# M507X.net
KiCad netlist of a schematic drawn in EAGLE
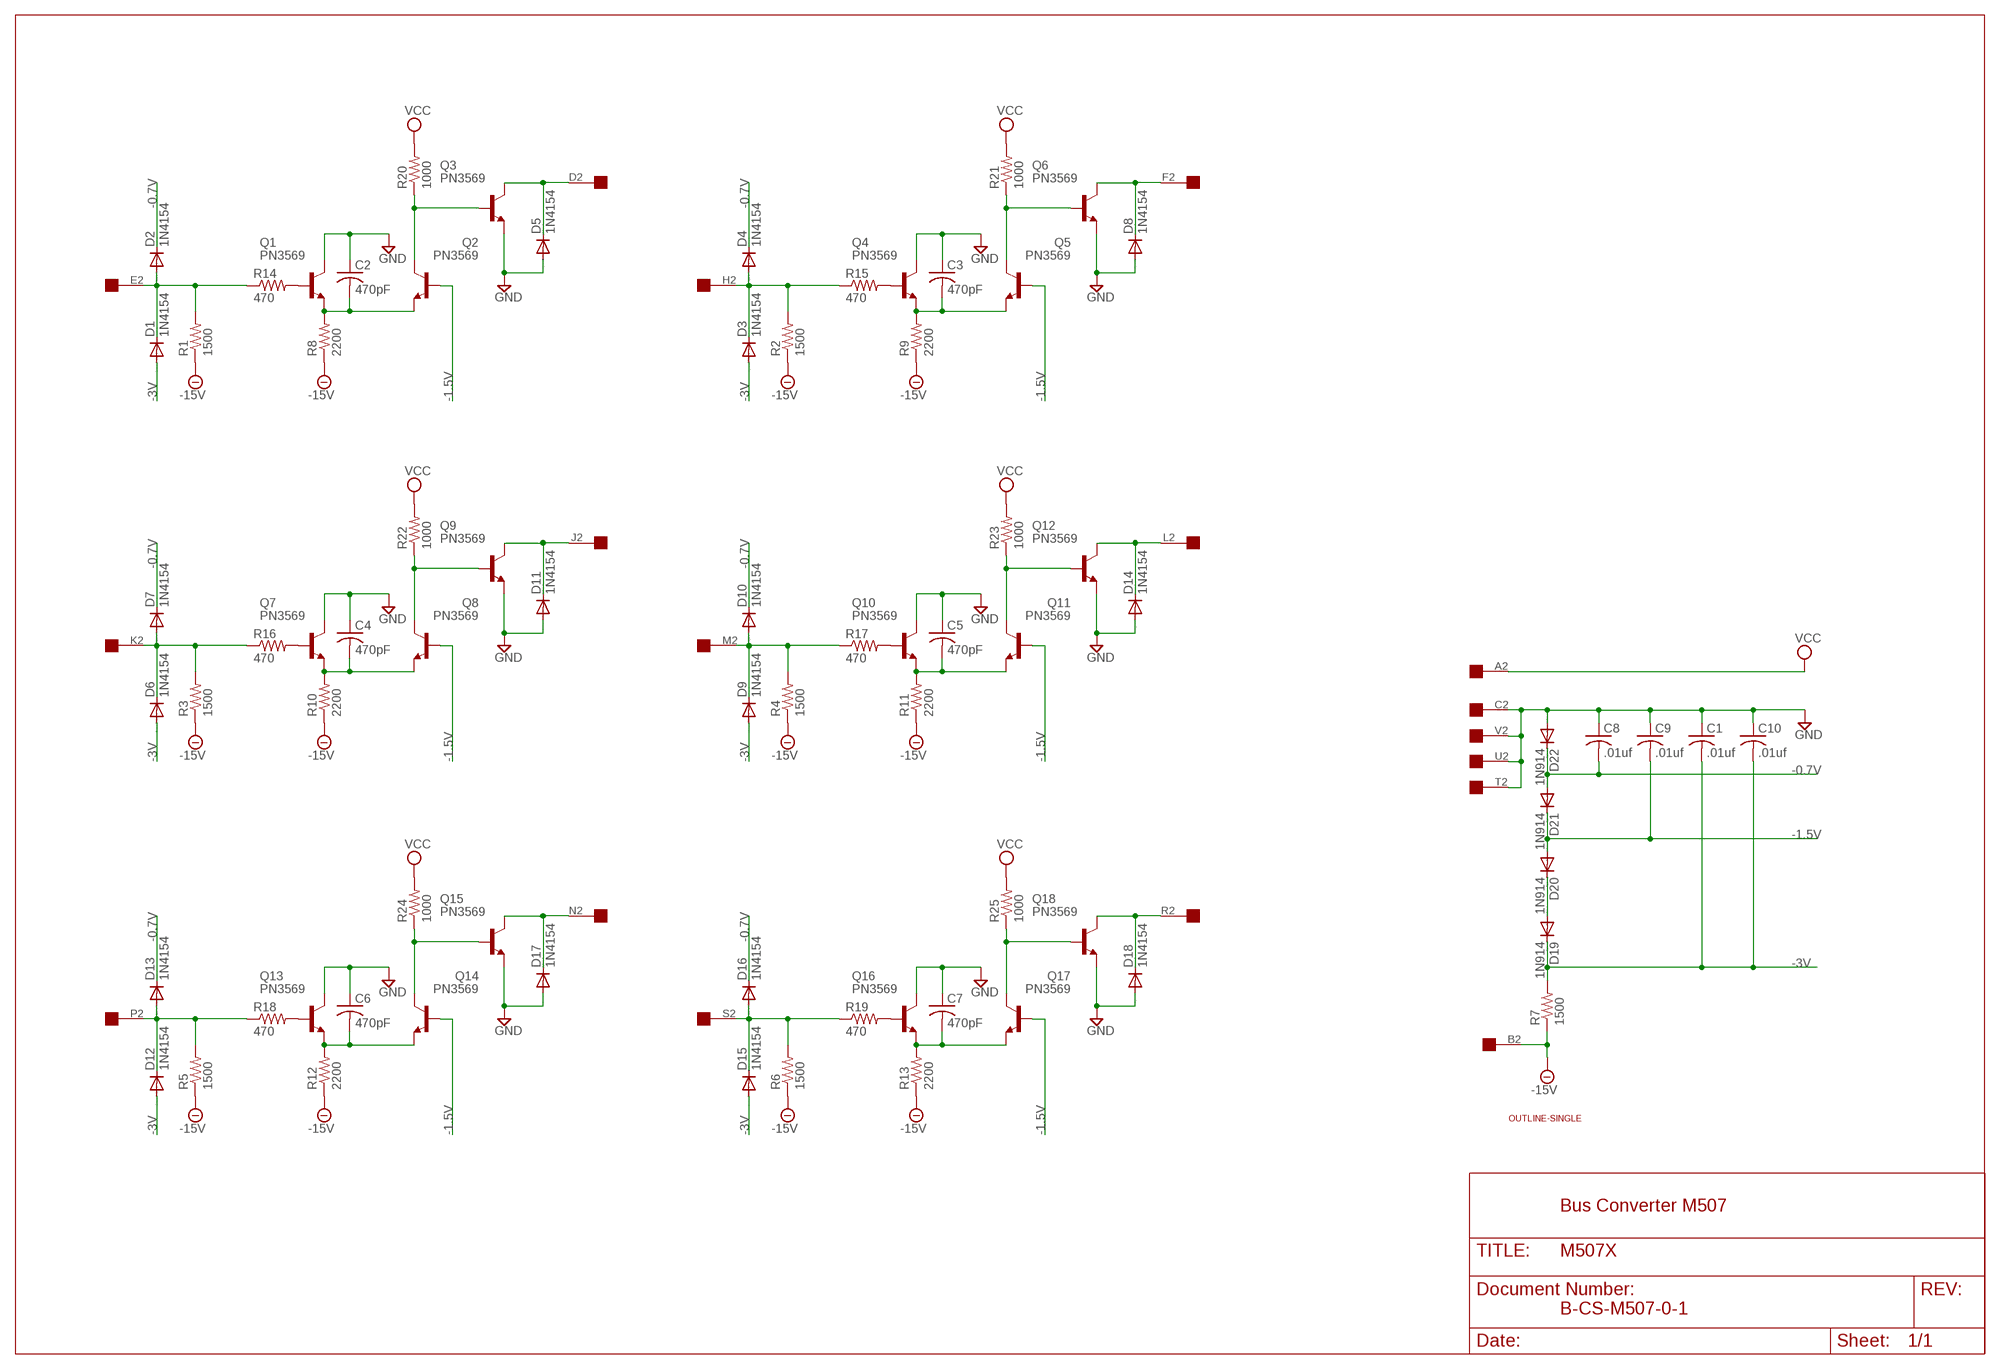
[diagram p0: schematic, sheet 1]

(export (version "E")
  (design (tool "Eeschema 10.0.6"))
  (components
    (comp (ref "C1")
      (value ".01uf")
      (footprint "eagle-import:C050-025X075")
      (libsource (lib "eagle-import") (part "C-US050-025X075"))
    )
    (comp (ref "C2")
      (value "470pF")
      (footprint "eagle-import:C050-025X075")
      (libsource (lib "eagle-import") (part "C-US050-025X075"))
    )
    (comp (ref "C3")
      (value "470pF")
      (footprint "eagle-import:C050-025X075")
      (libsource (lib "eagle-import") (part "C-US050-025X075"))
    )
    (comp (ref "C4")
      (value "470pF")
      (footprint "eagle-import:C050-025X075")
      (libsource (lib "eagle-import") (part "C-US050-025X075"))
    )
    (comp (ref "C5")
      (value "470pF")
      (footprint "eagle-import:C050-025X075")
      (libsource (lib "eagle-import") (part "C-US050-025X075"))
    )
    (comp (ref "C6")
      (value "470pF")
      (footprint "eagle-import:C050-025X075")
      (libsource (lib "eagle-import") (part "C-US050-025X075"))
    )
    (comp (ref "C7")
      (value "470pF")
      (footprint "eagle-import:C050-025X075")
      (libsource (lib "eagle-import") (part "C-US050-025X075"))
    )
    (comp (ref "C8")
      (value ".01uf")
      (footprint "eagle-import:C050-025X075")
      (libsource (lib "eagle-import") (part "C-US050-025X075"))
    )
    (comp (ref "C9")
      (value ".01uf")
      (footprint "eagle-import:C050-025X075")
      (libsource (lib "eagle-import") (part "C-US050-025X075"))
    )
    (comp (ref "C10")
      (value ".01uf")
      (footprint "eagle-import:C050-025X075")
      (libsource (lib "eagle-import") (part "C-US050-025X075"))
    )
    (comp (ref "D1")
      (value "1N4154")
      (footprint "eagle-import:DO35-10")
      (libsource (lib "eagle-import") (part "1N4148DO35-10"))
    )
    (comp (ref "D2")
      (value "1N4154")
      (footprint "eagle-import:DO35-10")
      (libsource (lib "eagle-import") (part "1N4148DO35-10"))
    )
    (comp (ref "D3")
      (value "1N4154")
      (footprint "eagle-import:DO35-10")
      (libsource (lib "eagle-import") (part "1N4148DO35-10"))
    )
    (comp (ref "D4")
      (value "1N4154")
      (footprint "eagle-import:DO35-10")
      (libsource (lib "eagle-import") (part "1N4148DO35-10"))
    )
    (comp (ref "D5")
      (value "1N4154")
      (footprint "eagle-import:DO35-10")
      (libsource (lib "eagle-import") (part "1N4148DO35-10"))
    )
    (comp (ref "D6")
      (value "1N4154")
      (footprint "eagle-import:DO35-10")
      (libsource (lib "eagle-import") (part "1N4148DO35-10"))
    )
    (comp (ref "D7")
      (value "1N4154")
      (footprint "eagle-import:DO35-10")
      (libsource (lib "eagle-import") (part "1N4148DO35-10"))
    )
    (comp (ref "D8")
      (value "1N4154")
      (footprint "eagle-import:DO35-10")
      (libsource (lib "eagle-import") (part "1N4148DO35-10"))
    )
    (comp (ref "D9")
      (value "1N4154")
      (footprint "eagle-import:DO35-10")
      (libsource (lib "eagle-import") (part "1N4148DO35-10"))
    )
    (comp (ref "D10")
      (value "1N4154")
      (footprint "eagle-import:DO35-10")
      (libsource (lib "eagle-import") (part "1N4148DO35-10"))
    )
    (comp (ref "D11")
      (value "1N4154")
      (footprint "eagle-import:DO35-10")
      (libsource (lib "eagle-import") (part "1N4148DO35-10"))
    )
    (comp (ref "D12")
      (value "1N4154")
      (footprint "eagle-import:DO35-10")
      (libsource (lib "eagle-import") (part "1N4148DO35-10"))
    )
    (comp (ref "D13")
      (value "1N4154")
      (footprint "eagle-import:DO35-10")
      (libsource (lib "eagle-import") (part "1N4148DO35-10"))
    )
    (comp (ref "D14")
      (value "1N4154")
      (footprint "eagle-import:DO35-10")
      (libsource (lib "eagle-import") (part "1N4148DO35-10"))
    )
    (comp (ref "D15")
      (value "1N4154")
      (footprint "eagle-import:DO35-10")
      (libsource (lib "eagle-import") (part "1N4148DO35-10"))
    )
    (comp (ref "D16")
      (value "1N4154")
      (footprint "eagle-import:DO35-10")
      (libsource (lib "eagle-import") (part "1N4148DO35-10"))
    )
    (comp (ref "D17")
      (value "1N4154")
      (footprint "eagle-import:DO35-10")
      (libsource (lib "eagle-import") (part "1N4148DO35-10"))
    )
    (comp (ref "D18")
      (value "1N4154")
      (footprint "eagle-import:DO35-10")
      (libsource (lib "eagle-import") (part "1N4148DO35-10"))
    )
    (comp (ref "D19")
      (value "1N914")
      (footprint "eagle-import:DO35-10")
      (libsource (lib "eagle-import") (part "1N4148DO35-10"))
    )
    (comp (ref "D20")
      (value "1N914")
      (footprint "eagle-import:DO35-10")
      (libsource (lib "eagle-import") (part "1N4148DO35-10"))
    )
    (comp (ref "D21")
      (value "1N914")
      (footprint "eagle-import:DO35-10")
      (libsource (lib "eagle-import") (part "1N4148DO35-10"))
    )
    (comp (ref "D22")
      (value "1N914")
      (footprint "eagle-import:DO35-10")
      (libsource (lib "eagle-import") (part "1N4148DO35-10"))
    )
    (comp (ref "Q1")
      (value "PN3569")
      (footprint "eagle-import:TO39")
      (libsource (lib "eagle-import") (part "2N3019"))
    )
    (comp (ref "Q2")
      (value "PN3569")
      (footprint "eagle-import:TO39")
      (libsource (lib "eagle-import") (part "2N3019"))
    )
    (comp (ref "Q3")
      (value "PN3569")
      (footprint "eagle-import:TO39")
      (libsource (lib "eagle-import") (part "2N3019"))
    )
    (comp (ref "Q4")
      (value "PN3569")
      (footprint "eagle-import:TO39")
      (libsource (lib "eagle-import") (part "2N3019"))
    )
    (comp (ref "Q5")
      (value "PN3569")
      (footprint "eagle-import:TO39")
      (libsource (lib "eagle-import") (part "2N3019"))
    )
    (comp (ref "Q6")
      (value "PN3569")
      (footprint "eagle-import:TO39")
      (libsource (lib "eagle-import") (part "2N3019"))
    )
    (comp (ref "Q7")
      (value "PN3569")
      (footprint "eagle-import:TO39")
      (libsource (lib "eagle-import") (part "2N3019"))
    )
    (comp (ref "Q8")
      (value "PN3569")
      (footprint "eagle-import:TO39")
      (libsource (lib "eagle-import") (part "2N3019"))
    )
    (comp (ref "Q9")
      (value "PN3569")
      (footprint "eagle-import:TO39")
      (libsource (lib "eagle-import") (part "2N3019"))
    )
    (comp (ref "Q10")
      (value "PN3569")
      (footprint "eagle-import:TO39")
      (libsource (lib "eagle-import") (part "2N3019"))
    )
    (comp (ref "Q11")
      (value "PN3569")
      (footprint "eagle-import:TO39")
      (libsource (lib "eagle-import") (part "2N3019"))
    )
    (comp (ref "Q12")
      (value "PN3569")
      (footprint "eagle-import:TO39")
      (libsource (lib "eagle-import") (part "2N3019"))
    )
    (comp (ref "Q13")
      (value "PN3569")
      (footprint "eagle-import:TO39")
      (libsource (lib "eagle-import") (part "2N3019"))
    )
    (comp (ref "Q14")
      (value "PN3569")
      (footprint "eagle-import:TO39")
      (libsource (lib "eagle-import") (part "2N3019"))
    )
    (comp (ref "Q15")
      (value "PN3569")
      (footprint "eagle-import:TO39")
      (libsource (lib "eagle-import") (part "2N3019"))
    )
    (comp (ref "Q16")
      (value "PN3569")
      (footprint "eagle-import:TO39")
      (libsource (lib "eagle-import") (part "2N3019"))
    )
    (comp (ref "Q17")
      (value "PN3569")
      (footprint "eagle-import:TO39")
      (libsource (lib "eagle-import") (part "2N3019"))
    )
    (comp (ref "Q18")
      (value "PN3569")
      (footprint "eagle-import:TO39")
      (libsource (lib "eagle-import") (part "2N3019"))
    )
    (comp (ref "R1")
      (value "1500")
      (footprint "eagle-import:0207_10")
      (libsource (lib "eagle-import") (part "R-US_0207/10"))
    )
    (comp (ref "R2")
      (value "1500")
      (footprint "eagle-import:0207_10")
      (libsource (lib "eagle-import") (part "R-US_0207/10"))
    )
    (comp (ref "R3")
      (value "1500")
      (footprint "eagle-import:0207_10")
      (libsource (lib "eagle-import") (part "R-US_0207/10"))
    )
    (comp (ref "R4")
      (value "1500")
      (footprint "eagle-import:0207_10")
      (libsource (lib "eagle-import") (part "R-US_0207/10"))
    )
    (comp (ref "R5")
      (value "1500")
      (footprint "eagle-import:0207_10")
      (libsource (lib "eagle-import") (part "R-US_0207/10"))
    )
    (comp (ref "R6")
      (value "1500")
      (footprint "eagle-import:0207_10")
      (libsource (lib "eagle-import") (part "R-US_0207/10"))
    )
    (comp (ref "R7")
      (value "1500")
      (footprint "eagle-import:0207_10")
      (libsource (lib "eagle-import") (part "R-US_0207/10"))
    )
    (comp (ref "R8")
      (value "2200")
      (footprint "eagle-import:0207_10")
      (libsource (lib "eagle-import") (part "R-US_0207/10"))
    )
    (comp (ref "R9")
      (value "2200")
      (footprint "eagle-import:0207_10")
      (libsource (lib "eagle-import") (part "R-US_0207/10"))
    )
    (comp (ref "R10")
      (value "2200")
      (footprint "eagle-import:0207_10")
      (libsource (lib "eagle-import") (part "R-US_0207/10"))
    )
    (comp (ref "R11")
      (value "2200")
      (footprint "eagle-import:0207_10")
      (libsource (lib "eagle-import") (part "R-US_0207/10"))
    )
    (comp (ref "R12")
      (value "2200")
      (footprint "eagle-import:0207_10")
      (libsource (lib "eagle-import") (part "R-US_0207/10"))
    )
    (comp (ref "R13")
      (value "2200")
      (footprint "eagle-import:0207_10")
      (libsource (lib "eagle-import") (part "R-US_0207/10"))
    )
    (comp (ref "R14")
      (value "470")
      (footprint "eagle-import:0207_10")
      (libsource (lib "eagle-import") (part "R-US_0207/10"))
    )
    (comp (ref "R15")
      (value "470")
      (footprint "eagle-import:0207_10")
      (libsource (lib "eagle-import") (part "R-US_0207/10"))
    )
    (comp (ref "R16")
      (value "470")
      (footprint "eagle-import:0207_10")
      (libsource (lib "eagle-import") (part "R-US_0207/10"))
    )
    (comp (ref "R17")
      (value "470")
      (footprint "eagle-import:0207_10")
      (libsource (lib "eagle-import") (part "R-US_0207/10"))
    )
    (comp (ref "R18")
      (value "470")
      (footprint "eagle-import:0207_10")
      (libsource (lib "eagle-import") (part "R-US_0207/10"))
    )
    (comp (ref "R19")
      (value "470")
      (footprint "eagle-import:0207_10")
      (libsource (lib "eagle-import") (part "R-US_0207/10"))
    )
    (comp (ref "R20")
      (value "1000")
      (footprint "eagle-import:0207_10")
      (libsource (lib "eagle-import") (part "R-US_0207/10"))
    )
    (comp (ref "R21")
      (value "1000")
      (footprint "eagle-import:0207_10")
      (libsource (lib "eagle-import") (part "R-US_0207/10"))
    )
    (comp (ref "R22")
      (value "1000")
      (footprint "eagle-import:0207_10")
      (libsource (lib "eagle-import") (part "R-US_0207/10"))
    )
    (comp (ref "R23")
      (value "1000")
      (footprint "eagle-import:0207_10")
      (libsource (lib "eagle-import") (part "R-US_0207/10"))
    )
    (comp (ref "R24")
      (value "1000")
      (footprint "eagle-import:0207_10")
      (libsource (lib "eagle-import") (part "R-US_0207/10"))
    )
    (comp (ref "R25")
      (value "1000")
      (footprint "eagle-import:0207_10")
      (libsource (lib "eagle-import") (part "R-US_0207/10"))
    )
    (comp (ref "U$3")
      (value "EDGE-1")
      (footprint "eagle-import:EDGE-CON1")
      (libsource (lib "eagle-import") (part "EDGE-1"))
    )
    (comp (ref "U$4")
      (value "OUTLINE-SINGLE")
      (footprint "eagle-import:SINGLE")
      (libsource (lib "eagle-import") (part "OUTLINE-SINGLE"))
    )
  )
  (nets
    (net (code "1") (name "-15V") (class "Default")
      (node (ref "R1") (pin "1") (pinfunction "1_1") (pintype "passive"))
      (node (ref "R10") (pin "1") (pinfunction "1_1") (pintype "passive"))
      (node (ref "R11") (pin "1") (pinfunction "1_1") (pintype "passive"))
      (node (ref "R12") (pin "1") (pinfunction "1_1") (pintype "passive"))
      (node (ref "R13") (pin "1") (pinfunction "1_1") (pintype "passive"))
      (node (ref "R2") (pin "1") (pinfunction "1_1") (pintype "passive"))
      (node (ref "R3") (pin "1") (pinfunction "1_1") (pintype "passive"))
      (node (ref "R4") (pin "1") (pinfunction "1_1") (pintype "passive"))
      (node (ref "R5") (pin "1") (pinfunction "1_1") (pintype "passive"))
      (node (ref "R6") (pin "1") (pinfunction "1_1") (pintype "passive"))
      (node (ref "R7") (pin "1") (pinfunction "1_1") (pintype "passive"))
      (node (ref "R8") (pin "1") (pinfunction "1_1") (pintype "passive"))
      (node (ref "R9") (pin "1") (pinfunction "1_1") (pintype "passive"))
      (node (ref "U$3") (pin "B2") (pinfunction "1_B2") (pintype "bidirectional"))
    )
    (net (code "2") (name "/-0.7V") (class "Default")
      (node (ref "C8") (pin "2") (pinfunction "2_2") (pintype "passive"))
      (node (ref "D10") (pin "C") (pinfunction "C_C") (pintype "passive"))
      (node (ref "D13") (pin "C") (pinfunction "C_C") (pintype "passive"))
      (node (ref "D16") (pin "C") (pinfunction "C_C") (pintype "passive"))
      (node (ref "D2") (pin "C") (pinfunction "C_C") (pintype "passive"))
      (node (ref "D21") (pin "A") (pinfunction "A_A") (pintype "passive"))
      (node (ref "D22") (pin "C") (pinfunction "C_C") (pintype "passive"))
      (node (ref "D4") (pin "C") (pinfunction "C_C") (pintype "passive"))
      (node (ref "D7") (pin "C") (pinfunction "C_C") (pintype "passive"))
    )
    (net (code "3") (name "/-1.5V") (class "Default")
      (node (ref "C9") (pin "2") (pinfunction "2_2") (pintype "passive"))
      (node (ref "D20") (pin "A") (pinfunction "A_A") (pintype "passive"))
      (node (ref "D21") (pin "C") (pinfunction "C_C") (pintype "passive"))
      (node (ref "Q11") (pin "2") (pinfunction "B_2") (pintype "passive"))
      (node (ref "Q14") (pin "2") (pinfunction "B_2") (pintype "passive"))
      (node (ref "Q17") (pin "2") (pinfunction "B_2") (pintype "passive"))
      (node (ref "Q2") (pin "2") (pinfunction "B_2") (pintype "passive"))
      (node (ref "Q5") (pin "2") (pinfunction "B_2") (pintype "passive"))
      (node (ref "Q8") (pin "2") (pinfunction "B_2") (pintype "passive"))
    )
    (net (code "4") (name "/-3V") (class "Default")
      (node (ref "C1") (pin "2") (pinfunction "2_2") (pintype "passive"))
      (node (ref "C10") (pin "2") (pinfunction "2_2") (pintype "passive"))
      (node (ref "D1") (pin "A") (pinfunction "A_A") (pintype "passive"))
      (node (ref "D12") (pin "A") (pinfunction "A_A") (pintype "passive"))
      (node (ref "D15") (pin "A") (pinfunction "A_A") (pintype "passive"))
      (node (ref "D19") (pin "C") (pinfunction "C_C") (pintype "passive"))
      (node (ref "D3") (pin "A") (pinfunction "A_A") (pintype "passive"))
      (node (ref "D6") (pin "A") (pinfunction "A_A") (pintype "passive"))
      (node (ref "D9") (pin "A") (pinfunction "A_A") (pintype "passive"))
      (node (ref "R7") (pin "2") (pinfunction "2_2") (pintype "passive"))
    )
    (net (code "5") (name "GND") (class "Default")
      (node (ref "C1") (pin "1") (pinfunction "1_1") (pintype "passive"))
      (node (ref "C10") (pin "1") (pinfunction "1_1") (pintype "passive"))
      (node (ref "C2") (pin "1") (pinfunction "1_1") (pintype "passive"))
      (node (ref "C3") (pin "1") (pinfunction "1_1") (pintype "passive"))
      (node (ref "C4") (pin "1") (pinfunction "1_1") (pintype "passive"))
      (node (ref "C5") (pin "1") (pinfunction "1_1") (pintype "passive"))
      (node (ref "C6") (pin "1") (pinfunction "1_1") (pintype "passive"))
      (node (ref "C7") (pin "1") (pinfunction "1_1") (pintype "passive"))
      (node (ref "C8") (pin "1") (pinfunction "1_1") (pintype "passive"))
      (node (ref "C9") (pin "1") (pinfunction "1_1") (pintype "passive"))
      (node (ref "D11") (pin "A") (pinfunction "A_A") (pintype "passive"))
      (node (ref "D14") (pin "A") (pinfunction "A_A") (pintype "passive"))
      (node (ref "D17") (pin "A") (pinfunction "A_A") (pintype "passive"))
      (node (ref "D18") (pin "A") (pinfunction "A_A") (pintype "passive"))
      (node (ref "D22") (pin "A") (pinfunction "A_A") (pintype "passive"))
      (node (ref "D5") (pin "A") (pinfunction "A_A") (pintype "passive"))
      (node (ref "D8") (pin "A") (pinfunction "A_A") (pintype "passive"))
      (node (ref "Q1") (pin "3") (pinfunction "C_3") (pintype "passive"))
      (node (ref "Q10") (pin "3") (pinfunction "C_3") (pintype "passive"))
      (node (ref "Q12") (pin "1") (pinfunction "E_1") (pintype "passive"))
      (node (ref "Q13") (pin "3") (pinfunction "C_3") (pintype "passive"))
      (node (ref "Q15") (pin "1") (pinfunction "E_1") (pintype "passive"))
      (node (ref "Q16") (pin "3") (pinfunction "C_3") (pintype "passive"))
      (node (ref "Q18") (pin "1") (pinfunction "E_1") (pintype "passive"))
      (node (ref "Q3") (pin "1") (pinfunction "E_1") (pintype "passive"))
      (node (ref "Q4") (pin "3") (pinfunction "C_3") (pintype "passive"))
      (node (ref "Q6") (pin "1") (pinfunction "E_1") (pintype "passive"))
      (node (ref "Q7") (pin "3") (pinfunction "C_3") (pintype "passive"))
      (node (ref "Q9") (pin "1") (pinfunction "E_1") (pintype "passive"))
      (node (ref "U$3") (pin "C2") (pinfunction "1_C2") (pintype "bidirectional"))
      (node (ref "U$3") (pin "T2") (pinfunction "1_T2") (pintype "bidirectional"))
      (node (ref "U$3") (pin "U2") (pinfunction "1_U2") (pintype "bidirectional"))
      (node (ref "U$3") (pin "V2") (pinfunction "1_V2") (pintype "bidirectional"))
    )
    (net (code "6") (name "Net-(D19-PadA)") (class "Default")
      (node (ref "D19") (pin "A") (pinfunction "A_A") (pintype "passive"))
      (node (ref "D20") (pin "C") (pinfunction "C_C") (pintype "passive"))
    )
    (net (code "7") (name "Net-(Q1-B)") (class "Default")
      (node (ref "Q1") (pin "2") (pinfunction "B_2") (pintype "passive"))
      (node (ref "R14") (pin "2") (pinfunction "2_2") (pintype "passive"))
    )
    (net (code "8") (name "Net-(Q1-E)") (class "Default")
      (node (ref "C2") (pin "2") (pinfunction "2_2") (pintype "passive"))
      (node (ref "Q1") (pin "1") (pinfunction "E_1") (pintype "passive"))
      (node (ref "Q2") (pin "1") (pinfunction "E_1") (pintype "passive"))
      (node (ref "R8") (pin "2") (pinfunction "2_2") (pintype "passive"))
    )
    (net (code "9") (name "Net-(Q2-C)") (class "Default")
      (node (ref "Q2") (pin "3") (pinfunction "C_3") (pintype "passive"))
      (node (ref "Q3") (pin "2") (pinfunction "B_2") (pintype "passive"))
      (node (ref "R20") (pin "1") (pinfunction "1_1") (pintype "passive"))
    )
    (net (code "10") (name "Net-(Q3-C)") (class "Default")
      (node (ref "D5") (pin "C") (pinfunction "C_C") (pintype "passive"))
      (node (ref "Q3") (pin "3") (pinfunction "C_3") (pintype "passive"))
      (node (ref "U$3") (pin "D2") (pinfunction "1_D2") (pintype "bidirectional"))
    )
    (net (code "11") (name "Net-(Q4-B)") (class "Default")
      (node (ref "Q4") (pin "2") (pinfunction "B_2") (pintype "passive"))
      (node (ref "R15") (pin "2") (pinfunction "2_2") (pintype "passive"))
    )
    (net (code "12") (name "Net-(Q4-E)") (class "Default")
      (node (ref "C3") (pin "2") (pinfunction "2_2") (pintype "passive"))
      (node (ref "Q4") (pin "1") (pinfunction "E_1") (pintype "passive"))
      (node (ref "Q5") (pin "1") (pinfunction "E_1") (pintype "passive"))
      (node (ref "R9") (pin "2") (pinfunction "2_2") (pintype "passive"))
    )
    (net (code "13") (name "Net-(Q5-C)") (class "Default")
      (node (ref "Q5") (pin "3") (pinfunction "C_3") (pintype "passive"))
      (node (ref "Q6") (pin "2") (pinfunction "B_2") (pintype "passive"))
      (node (ref "R21") (pin "1") (pinfunction "1_1") (pintype "passive"))
    )
    (net (code "14") (name "Net-(Q6-C)") (class "Default")
      (node (ref "D8") (pin "C") (pinfunction "C_C") (pintype "passive"))
      (node (ref "Q6") (pin "3") (pinfunction "C_3") (pintype "passive"))
      (node (ref "U$3") (pin "F2") (pinfunction "1_F2") (pintype "bidirectional"))
    )
    (net (code "15") (name "Net-(Q7-B)") (class "Default")
      (node (ref "Q7") (pin "2") (pinfunction "B_2") (pintype "passive"))
      (node (ref "R16") (pin "2") (pinfunction "2_2") (pintype "passive"))
    )
    (net (code "16") (name "Net-(Q7-E)") (class "Default")
      (node (ref "C4") (pin "2") (pinfunction "2_2") (pintype "passive"))
      (node (ref "Q7") (pin "1") (pinfunction "E_1") (pintype "passive"))
      (node (ref "Q8") (pin "1") (pinfunction "E_1") (pintype "passive"))
      (node (ref "R10") (pin "2") (pinfunction "2_2") (pintype "passive"))
    )
    (net (code "17") (name "Net-(Q8-C)") (class "Default")
      (node (ref "Q8") (pin "3") (pinfunction "C_3") (pintype "passive"))
      (node (ref "Q9") (pin "2") (pinfunction "B_2") (pintype "passive"))
      (node (ref "R22") (pin "1") (pinfunction "1_1") (pintype "passive"))
    )
    (net (code "18") (name "Net-(Q9-C)") (class "Default")
      (node (ref "D11") (pin "C") (pinfunction "C_C") (pintype "passive"))
      (node (ref "Q9") (pin "3") (pinfunction "C_3") (pintype "passive"))
      (node (ref "U$3") (pin "J2") (pinfunction "1_J2") (pintype "bidirectional"))
    )
    (net (code "19") (name "Net-(Q10-B)") (class "Default")
      (node (ref "Q10") (pin "2") (pinfunction "B_2") (pintype "passive"))
      (node (ref "R17") (pin "2") (pinfunction "2_2") (pintype "passive"))
    )
    (net (code "20") (name "Net-(Q10-E)") (class "Default")
      (node (ref "C5") (pin "2") (pinfunction "2_2") (pintype "passive"))
      (node (ref "Q10") (pin "1") (pinfunction "E_1") (pintype "passive"))
      (node (ref "Q11") (pin "1") (pinfunction "E_1") (pintype "passive"))
      (node (ref "R11") (pin "2") (pinfunction "2_2") (pintype "passive"))
    )
    (net (code "21") (name "Net-(Q11-C)") (class "Default")
      (node (ref "Q11") (pin "3") (pinfunction "C_3") (pintype "passive"))
      (node (ref "Q12") (pin "2") (pinfunction "B_2") (pintype "passive"))
      (node (ref "R23") (pin "1") (pinfunction "1_1") (pintype "passive"))
    )
    (net (code "22") (name "Net-(Q12-C)") (class "Default")
      (node (ref "D14") (pin "C") (pinfunction "C_C") (pintype "passive"))
      (node (ref "Q12") (pin "3") (pinfunction "C_3") (pintype "passive"))
      (node (ref "U$3") (pin "L2") (pinfunction "1_L2") (pintype "bidirectional"))
    )
    (net (code "23") (name "Net-(Q13-B)") (class "Default")
      (node (ref "Q13") (pin "2") (pinfunction "B_2") (pintype "passive"))
      (node (ref "R18") (pin "2") (pinfunction "2_2") (pintype "passive"))
    )
    (net (code "24") (name "Net-(Q13-E)") (class "Default")
      (node (ref "C6") (pin "2") (pinfunction "2_2") (pintype "passive"))
      (node (ref "Q13") (pin "1") (pinfunction "E_1") (pintype "passive"))
      (node (ref "Q14") (pin "1") (pinfunction "E_1") (pintype "passive"))
      (node (ref "R12") (pin "2") (pinfunction "2_2") (pintype "passive"))
    )
    (net (code "25") (name "Net-(Q14-C)") (class "Default")
      (node (ref "Q14") (pin "3") (pinfunction "C_3") (pintype "passive"))
      (node (ref "Q15") (pin "2") (pinfunction "B_2") (pintype "passive"))
      (node (ref "R24") (pin "1") (pinfunction "1_1") (pintype "passive"))
    )
    (net (code "26") (name "Net-(Q15-C)") (class "Default")
      (node (ref "D17") (pin "C") (pinfunction "C_C") (pintype "passive"))
      (node (ref "Q15") (pin "3") (pinfunction "C_3") (pintype "passive"))
      (node (ref "U$3") (pin "N2") (pinfunction "1_N2") (pintype "bidirectional"))
    )
    (net (code "27") (name "Net-(Q16-B)") (class "Default")
      (node (ref "Q16") (pin "2") (pinfunction "B_2") (pintype "passive"))
      (node (ref "R19") (pin "2") (pinfunction "2_2") (pintype "passive"))
    )
    (net (code "28") (name "Net-(Q16-E)") (class "Default")
      (node (ref "C7") (pin "2") (pinfunction "2_2") (pintype "passive"))
      (node (ref "Q16") (pin "1") (pinfunction "E_1") (pintype "passive"))
      (node (ref "Q17") (pin "1") (pinfunction "E_1") (pintype "passive"))
      (node (ref "R13") (pin "2") (pinfunction "2_2") (pintype "passive"))
    )
    (net (code "29") (name "Net-(Q17-C)") (class "Default")
      (node (ref "Q17") (pin "3") (pinfunction "C_3") (pintype "passive"))
      (node (ref "Q18") (pin "2") (pinfunction "B_2") (pintype "passive"))
      (node (ref "R25") (pin "1") (pinfunction "1_1") (pintype "passive"))
    )
    (net (code "30") (name "Net-(Q18-C)") (class "Default")
      (node (ref "D18") (pin "C") (pinfunction "C_C") (pintype "passive"))
      (node (ref "Q18") (pin "3") (pinfunction "C_3") (pintype "passive"))
      (node (ref "U$3") (pin "R2") (pinfunction "1_R2") (pintype "bidirectional"))
    )
    (net (code "31") (name "Net-(U$3E-1)") (class "Default")
      (node (ref "D1") (pin "C") (pinfunction "C_C") (pintype "passive"))
      (node (ref "D2") (pin "A") (pinfunction "A_A") (pintype "passive"))
      (node (ref "R1") (pin "2") (pinfunction "2_2") (pintype "passive"))
      (node (ref "R14") (pin "1") (pinfunction "1_1") (pintype "passive"))
      (node (ref "U$3") (pin "E2") (pinfunction "1_E2") (pintype "bidirectional"))
    )
    (net (code "32") (name "Net-(U$3G-1)") (class "Default")
      (node (ref "D3") (pin "C") (pinfunction "C_C") (pintype "passive"))
      (node (ref "D4") (pin "A") (pinfunction "A_A") (pintype "passive"))
      (node (ref "R15") (pin "1") (pinfunction "1_1") (pintype "passive"))
      (node (ref "R2") (pin "2") (pinfunction "2_2") (pintype "passive"))
      (node (ref "U$3") (pin "H2") (pinfunction "1_H2") (pintype "bidirectional"))
    )
    (net (code "33") (name "Net-(U$3I-1)") (class "Default")
      (node (ref "D6") (pin "C") (pinfunction "C_C") (pintype "passive"))
      (node (ref "D7") (pin "A") (pinfunction "A_A") (pintype "passive"))
      (node (ref "R16") (pin "1") (pinfunction "1_1") (pintype "passive"))
      (node (ref "R3") (pin "2") (pinfunction "2_2") (pintype "passive"))
      (node (ref "U$3") (pin "K2") (pinfunction "1_K2") (pintype "bidirectional"))
    )
    (net (code "34") (name "Net-(U$3K-1)") (class "Default")
      (node (ref "D10") (pin "A") (pinfunction "A_A") (pintype "passive"))
      (node (ref "D9") (pin "C") (pinfunction "C_C") (pintype "passive"))
      (node (ref "R17") (pin "1") (pinfunction "1_1") (pintype "passive"))
      (node (ref "R4") (pin "2") (pinfunction "2_2") (pintype "passive"))
      (node (ref "U$3") (pin "M2") (pinfunction "1_M2") (pintype "bidirectional"))
    )
    (net (code "35") (name "Net-(U$3M-1)") (class "Default")
      (node (ref "D12") (pin "C") (pinfunction "C_C") (pintype "passive"))
      (node (ref "D13") (pin "A") (pinfunction "A_A") (pintype "passive"))
      (node (ref "R18") (pin "1") (pinfunction "1_1") (pintype "passive"))
      (node (ref "R5") (pin "2") (pinfunction "2_2") (pintype "passive"))
      (node (ref "U$3") (pin "P2") (pinfunction "1_P2") (pintype "bidirectional"))
    )
    (net (code "36") (name "Net-(U$3O-1)") (class "Default")
      (node (ref "D15") (pin "C") (pinfunction "C_C") (pintype "passive"))
      (node (ref "D16") (pin "A") (pinfunction "A_A") (pintype "passive"))
      (node (ref "R19") (pin "1") (pinfunction "1_1") (pintype "passive"))
      (node (ref "R6") (pin "2") (pinfunction "2_2") (pintype "passive"))
      (node (ref "U$3") (pin "S2") (pinfunction "1_S2") (pintype "bidirectional"))
    )
    (net (code "37") (name "VCC") (class "Default")
      (node (ref "R20") (pin "2") (pinfunction "2_2") (pintype "passive"))
      (node (ref "R21") (pin "2") (pinfunction "2_2") (pintype "passive"))
      (node (ref "R22") (pin "2") (pinfunction "2_2") (pintype "passive"))
      (node (ref "R23") (pin "2") (pinfunction "2_2") (pintype "passive"))
      (node (ref "R24") (pin "2") (pinfunction "2_2") (pintype "passive"))
      (node (ref "R25") (pin "2") (pinfunction "2_2") (pintype "passive"))
      (node (ref "U$3") (pin "A2") (pinfunction "1_A2") (pintype "bidirectional"))
    )
  )
)
